# 05_Connectors_LDO_EEPROM.net
KiCad netlist of a schematic drawn in Altium Designer
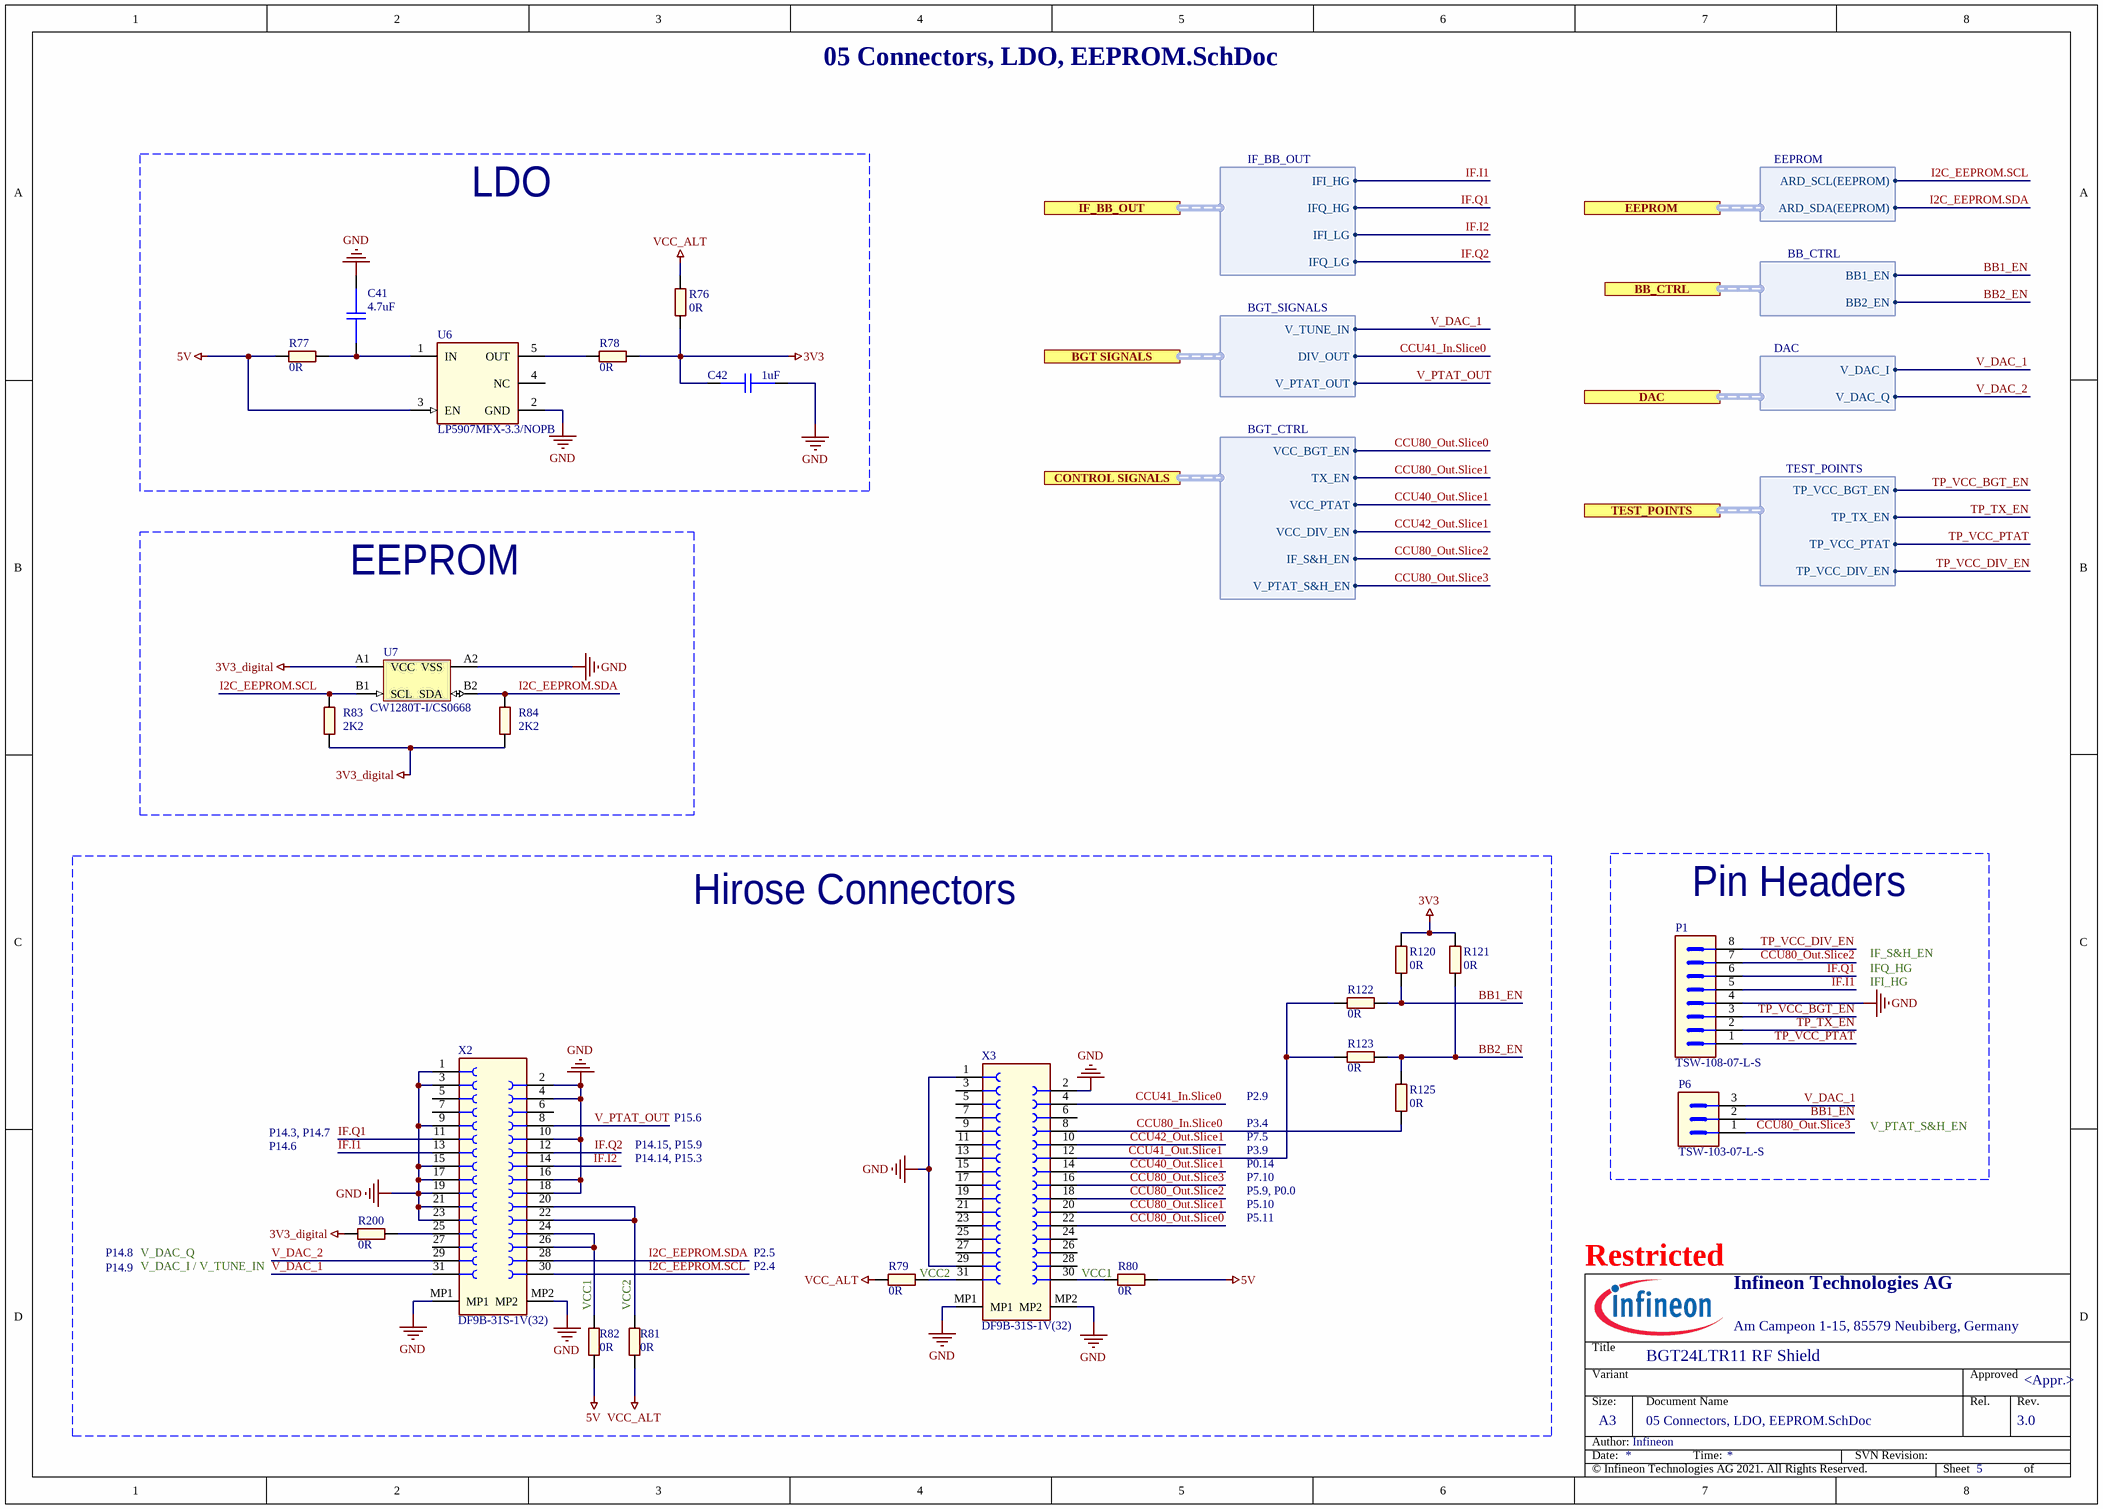
[diagram p0: 05 Connectors, LDO, EEPROM.SchDoc]

(export (version "E")
  (design (tool "Eeschema 10.0.6"))
  (components
    (comp (ref "C41")
      (value "4.7uF")
      (footprint "CAPC1005X55N-0_2")
      (description "General Purpose Surface Mount Ceramic Capacitor")
      (fields (field (name "PARTNUMBER") "CAP01010597") (field (name "VOLTAGE") "50Vdc"))
      (libsource (lib "DB_External_Capacitor") (part "c_std_a"))
    )
    (comp (ref "C42")
      (value "1uF")
      (footprint "CAPC1005X55N-0_2")
      (description "General Purpose Surface Mount Ceramic Capacitor")
      (fields (field (name "PARTNUMBER") "CAP01010597") (field (name "VOLTAGE") "50Vdc"))
      (libsource (lib "DB_External_Capacitor") (part "c_std_a"))
    )
    (comp (ref "P1")
      (value "TSW-108-07-L-S")
      (footprint "CON-M-THT-TSW-108-07-L-S")
      (description "Through hole .025'' SQ Post Header, 2.54mm pitch, 8 pin, vertical, single row")
      (fields (field (name "LEGACY PARTNUMBER") "CON01500577") (field (name "MANUFACTURER") "Samtec"))
      (libsource (lib "PCBLibraryData") (part "Header 8"))
    )
    (comp (ref "P6")
      (value "TSW-103-07-L-S")
      (footprint "CON-M-THT-TSW-103-07-L-S")
      (description "Through hole .025 SQ Post Header, 2.54mm pitch, 3 pin, vertical, single row")
      (fields (field (name "LEGACY PARTNUMBER") "CON01500575") (field (name "MANUFACTURER") "Samtec"))
      (libsource (lib "PCBLibraryData") (part "Header 3"))
    )
    (comp (ref "R76")
      (value "0R")
      (footprint "RESC1005X40N_2")
      (description "0R/50V/20mOhm")
      (fields (field (name "PARTNUMBER") "RES01800000") (field (name "POWER") "1.5A"))
      (libsource (lib "") (part "r_std_a_1"))
    )
    (comp (ref "R77")
      (value "0R")
      (footprint "RESC1005X40N_2")
      (description "0R/50V/20mOhm")
      (fields (field (name "PARTNUMBER") "RES01800000") (field (name "POWER") "1.5A"))
      (libsource (lib "") (part "r_std_a_2"))
    )
    (comp (ref "R78")
      (value "0R")
      (footprint "RESC1005X40N_2")
      (description "0R/50V/20mOhm")
      (fields (field (name "PARTNUMBER") "RES01800000") (field (name "POWER") "1.5A"))
      (libsource (lib "") (part "r_std_a_2"))
    )
    (comp (ref "R79")
      (value "0R")
      (footprint "RESC1005X40N_2")
      (description "0R/50V/20mOhm")
      (fields (field (name "PARTNUMBER") "RES01800000") (field (name "POWER") "1.5A"))
      (libsource (lib "") (part "r_std_a_3"))
    )
    (comp (ref "R80")
      (value "0R")
      (footprint "RESC1005X40N_2")
      (description "0R/50V/20mOhm")
      (fields (field (name "PARTNUMBER") "RES01800000") (field (name "POWER") "1.5A"))
      (libsource (lib "") (part "r_std_a_2"))
    )
    (comp (ref "R81")
      (value "0R")
      (footprint "RESC1005X40N_2")
      (description "0R/50V/20mOhm")
      (fields (field (name "PARTNUMBER") "RES01800000") (field (name "POWER") "1.5A"))
      (libsource (lib "DB_External_Resistor") (part "r_std_a"))
    )
    (comp (ref "R82")
      (value "0R")
      (footprint "RESC1005X40N_2")
      (description "0R/50V/20mOhm")
      (fields (field (name "PARTNUMBER") "RES01800000") (field (name "POWER") "1.5A"))
      (libsource (lib "DB_External_Resistor") (part "r_std_a"))
    )
    (comp (ref "R83")
      (value "2K2")
      (footprint "RESC1005X40N_2")
      (description "2K2/50V/20mOhm")
      (fields (field (name "PARTNUMBER") "RES01800000") (field (name "POWER") "1.5A"))
      (libsource (lib "") (part "r_std_a_1"))
    )
    (comp (ref "R84")
      (value "2K2")
      (footprint "RESC1005X40N_2")
      (description "2K2/50V/20mOhm")
      (fields (field (name "PARTNUMBER") "RES01800000") (field (name "POWER") "1.5A"))
      (libsource (lib "") (part "r_std_a_1"))
    )
    (comp (ref "R120")
      (value "0R")
      (footprint "RESC1005X40N_2")
      (description "0R/50V/20mOhm")
      (fields (field (name "PARTNUMBER") "RES01800000") (field (name "POWER") "1.5A"))
      (libsource (lib "") (part "r_std_a_1"))
    )
    (comp (ref "R121")
      (value "0R")
      (footprint "RESC1005X40N_2")
      (description "0R/50V/20mOhm")
      (fields (field (name "PARTNUMBER") "RES01800000") (field (name "POWER") "1.5A"))
      (libsource (lib "") (part "r_std_a_1"))
    )
    (comp (ref "R122")
      (value "0R")
      (footprint "RESC1005X40N_2")
      (description "0R/50V/20mOhm")
      (fields (field (name "PARTNUMBER") "RES01800000") (field (name "POWER") "1.5A"))
      (libsource (lib "") (part "r_std_a_2"))
    )
    (comp (ref "R123")
      (value "0R")
      (footprint "RESC1005X40N_2")
      (description "0R/50V/20mOhm")
      (fields (field (name "PARTNUMBER") "RES01800000") (field (name "POWER") "1.5A"))
      (libsource (lib "") (part "r_std_a_2"))
    )
    (comp (ref "R125")
      (value "0R")
      (footprint "RESC1005X40N_2")
      (description "0R/50V/20mOhm")
      (fields (field (name "PARTNUMBER") "RES01800000") (field (name "POWER") "1.5A"))
      (libsource (lib "") (part "r_std_a_1"))
    )
    (comp (ref "R200")
      (value "0R")
      (footprint "RESC1005X40N_2")
      (description "0R/50V/20mOhm")
      (fields (field (name "PARTNUMBER") "RES01800000") (field (name "POWER") "1.5A"))
      (libsource (lib "") (part "r_std_a_2"))
    )
    (comp (ref "U6")
      (value "LP5907MFX-3.3/NOPB")
      (footprint "SOT95P280X145-5N-2")
      (description "250mA Ultra-Low-Noise, Low-IQ LDO, 3.3V")
      (fields
        (field (name "PARTNUMBER") "IC02601280")
        (field (name "COMPONENTNAME") "LP5907MFX-3.3/NOPB")
        (field (name "MANUFACTURER") "Texas Instruments")
      )
      (libsource (lib "DB_External_IC") (part "LP5907MFX"))
    )
    (comp (ref "U7")
      (value "CW1280T-I/CS0668")
      (footprint "WLCSP4 (CS0)")
      (description "128K I2C Serial EEPROM with Software Write Protection in CSP4 Package, 0.4mm Pin Pitch")
      (libsource (lib "BGT24LTR11 RF-Shield Board V0.3") (part "24CW128X"))
    )
    (comp (ref "X2")
      (value "DF9B-31S-1V(32)")
      (footprint "CON-F-SMD-DF9B-31S-1V-32-1")
      (description "SMT Board-to-Board connectors-standard interface connector")
      (fields (field (name "MANUFACTURER") "Hirose Connectors"))
      (libsource (lib "PCBLibraryData") (part "CON-SOC-016X002-0031P-02S-00M_00080644"))
    )
    (comp (ref "X3")
      (value "DF9B-31S-1V(32)")
      (footprint "CON-F-SMD-DF9B-31S-1V-32-1")
      (description "SMT Board-to-Board connectors-standard interface connector")
      (fields (field (name "MANUFACTURER") "Hirose Connectors"))
      (libsource (lib "PCBLibraryData") (part "CON-SOC-016X002-0031P-02S-00M_00080644"))
    )
  )
  (nets
    (net (code "8") (name "/BB1_EN") (class "Default")
      (node (ref "P6") (pin "2") (pinfunction "2_2") (pintype "passive"))
      (node (ref "R120") (pin "2") (pinfunction "2_2") (pintype "passive"))
      (node (ref "R122") (pin "1") (pinfunction "1_1") (pintype "passive"))
    )
    (net (code "9") (name "/BB2_EN") (class "Default")
      (node (ref "R121") (pin "2") (pinfunction "2_2") (pintype "passive"))
      (node (ref "R123") (pin "1") (pinfunction "1_1") (pintype "passive"))
      (node (ref "R125") (pin "1") (pinfunction "1_1") (pintype "passive"))
    )
    (net (code "10") (name "/CCU40_Out.Slice1") (class "Default")
      (node (ref "X3") (pin "14") (pinfunction "14_14") (pintype "passive"))
    )
    (net (code "11") (name "/CCU41_In.Slice0") (class "Default")
      (node (ref "X3") (pin "4") (pinfunction "4_4") (pintype "passive"))
    )
    (net (code "12") (name "/CCU41_Out.Slice1") (class "Default")
      (node (ref "R122") (pin "2") (pinfunction "2_2") (pintype "passive"))
      (node (ref "R123") (pin "2") (pinfunction "2_2") (pintype "passive"))
      (node (ref "X3") (pin "12") (pinfunction "12_12") (pintype "passive"))
    )
    (net (code "13") (name "/CCU42_Out.Slice1") (class "Default")
      (node (ref "X3") (pin "10") (pinfunction "10_10") (pintype "passive"))
    )
    (net (code "14") (name "/CCU80_In.Slice0") (class "Default")
      (node (ref "R125") (pin "2") (pinfunction "2_2") (pintype "passive"))
      (node (ref "X3") (pin "8") (pinfunction "8_8") (pintype "passive"))
    )
    (net (code "15") (name "/CCU80_Out.Slice0") (class "Default")
      (node (ref "X3") (pin "22") (pinfunction "22_22") (pintype "passive"))
    )
    (net (code "16") (name "/CCU80_Out.Slice1") (class "Default")
      (node (ref "X3") (pin "20") (pinfunction "20_20") (pintype "passive"))
    )
    (net (code "17") (name "/CCU80_Out.Slice2") (class "Default")
      (node (ref "P1") (pin "7") (pinfunction "7_7") (pintype "passive"))
      (node (ref "X3") (pin "18") (pinfunction "18_18") (pintype "passive"))
    )
    (net (code "18") (name "/CCU80_Out.Slice3") (class "Default")
      (node (ref "P6") (pin "1") (pinfunction "1_1") (pintype "passive"))
      (node (ref "X3") (pin "16") (pinfunction "16_16") (pintype "passive"))
    )
    (net (code "19") (name "/I2C_EEPROM.SCL") (class "Default")
      (node (ref "R83") (pin "1") (pinfunction "1_1") (pintype "passive"))
      (node (ref "U7") (pin "B1") (pinfunction "SCL_B1") (pintype "input"))
      (node (ref "X2") (pin "30") (pinfunction "30_30") (pintype "passive"))
    )
    (net (code "20") (name "/I2C_EEPROM.SDA") (class "Default")
      (node (ref "R84") (pin "1") (pinfunction "1_1") (pintype "passive"))
      (node (ref "U7") (pin "B2") (pinfunction "SDA_B2") (pintype "bidirectional"))
      (node (ref "X2") (pin "28") (pinfunction "28_28") (pintype "passive"))
    )
    (net (code "21") (name "/IF.I1") (class "Default")
      (node (ref "P1") (pin "5") (pinfunction "5_5") (pintype "passive"))
      (node (ref "X2") (pin "13") (pinfunction "13_13") (pintype "passive"))
    )
    (net (code "22") (name "/IF.I2") (class "Default")
      (node (ref "X2") (pin "14") (pinfunction "14_14") (pintype "passive"))
    )
    (net (code "23") (name "/IF.Q1") (class "Default")
      (node (ref "P1") (pin "6") (pinfunction "6_6") (pintype "passive"))
      (node (ref "X2") (pin "11") (pinfunction "11_11") (pintype "passive"))
    )
    (net (code "24") (name "/IF.Q2") (class "Default")
      (node (ref "X2") (pin "12") (pinfunction "12_12") (pintype "passive"))
    )
    (net (code "25") (name "/TP_TX_EN") (class "Default")
      (node (ref "P1") (pin "2") (pinfunction "2_2") (pintype "passive"))
    )
    (net (code "26") (name "/TP_VCC_BGT_EN") (class "Default")
      (node (ref "P1") (pin "3") (pinfunction "3_3") (pintype "passive"))
    )
    (net (code "27") (name "/TP_VCC_DIV_EN") (class "Default")
      (node (ref "P1") (pin "8") (pinfunction "8_8") (pintype "passive"))
    )
    (net (code "28") (name "/TP_VCC_PTAT") (class "Default")
      (node (ref "P1") (pin "1") (pinfunction "1_1") (pintype "passive"))
    )
    (net (code "29") (name "/V_DAC_1") (class "Default")
      (node (ref "P6") (pin "3") (pinfunction "3_3") (pintype "passive"))
      (node (ref "X2") (pin "31") (pinfunction "31_31") (pintype "passive"))
    )
    (net (code "30") (name "/V_DAC_2") (class "Default")
      (node (ref "X2") (pin "29") (pinfunction "29_29") (pintype "passive"))
    )
    (net (code "31") (name "/V_PTAT_OUT") (class "Default")
      (node (ref "X2") (pin "8") (pinfunction "8_8") (pintype "passive"))
    )
    (net (code "39") (name "3V3") (class "Default")
      (node (ref "C42") (pin "2") (pinfunction "2_2") (pintype "passive"))
      (node (ref "R120") (pin "1") (pinfunction "1_1") (pintype "passive"))
      (node (ref "R121") (pin "1") (pinfunction "1_1") (pintype "passive"))
      (node (ref "R76") (pin "2") (pinfunction "2_2") (pintype "passive"))
      (node (ref "R78") (pin "1") (pinfunction "1_1") (pintype "passive"))
    )
    (net (code "40") (name "3V3_digital") (class "Default")
      (node (ref "R200") (pin "2") (pinfunction "2_2") (pintype "passive"))
      (node (ref "R83") (pin "2") (pinfunction "2_2") (pintype "passive"))
      (node (ref "R84") (pin "2") (pinfunction "2_2") (pintype "passive"))
      (node (ref "U7") (pin "A1") (pinfunction "VCC_A1") (pintype "passive"))
    )
    (net (code "41") (name "5V") (class "Default")
      (node (ref "R77") (pin "2") (pinfunction "2_2") (pintype "passive"))
      (node (ref "R80") (pin "1") (pinfunction "1_1") (pintype "passive"))
      (node (ref "R82") (pin "1") (pinfunction "1_1") (pintype "passive"))
      (node (ref "U6") (pin "3") (pinfunction "EN_3") (pintype "input"))
    )
    (net (code "42") (name "GND") (class "Default")
      (node (ref "C41") (pin "1") (pinfunction "1_1") (pintype "passive"))
      (node (ref "C42") (pin "1") (pinfunction "1_1") (pintype "passive"))
      (node (ref "P1") (pin "4") (pinfunction "4_4") (pintype "passive"))
      (node (ref "U6") (pin "2") (pinfunction "GND_2") (pintype "power_in"))
      (node (ref "U7") (pin "A2") (pinfunction "VSS_A2") (pintype "passive"))
      (node (ref "X2") (pin "1") (pinfunction "1_1") (pintype "passive"))
      (node (ref "X2") (pin "10") (pinfunction "10_10") (pintype "passive"))
      (node (ref "X2") (pin "15") (pinfunction "15_15") (pintype "passive"))
      (node (ref "X2") (pin "16") (pinfunction "16_16") (pintype "passive"))
      (node (ref "X2") (pin "17") (pinfunction "17_17") (pintype "passive"))
      (node (ref "X2") (pin "18") (pinfunction "18_18") (pintype "passive"))
      (node (ref "X2") (pin "19") (pinfunction "19_19") (pintype "passive"))
      (node (ref "X2") (pin "2") (pinfunction "2_2") (pintype "passive"))
      (node (ref "X2") (pin "21") (pinfunction "21_21") (pintype "passive"))
      (node (ref "X2") (pin "23") (pinfunction "23_23") (pintype "passive"))
      (node (ref "X2") (pin "3") (pinfunction "3_3") (pintype "passive"))
      (node (ref "X2") (pin "4") (pinfunction "4_4") (pintype "passive"))
      (node (ref "X2") (pin "9") (pinfunction "9_9") (pintype "passive"))
      (node (ref "X2") (pin "MP1") (pinfunction "MP1_MP1") (pintype "passive"))
      (node (ref "X2") (pin "MP2") (pinfunction "MP2_MP2") (pintype "passive"))
      (node (ref "X3") (pin "1") (pinfunction "1_1") (pintype "passive"))
      (node (ref "X3") (pin "2") (pinfunction "2_2") (pintype "passive"))
      (node (ref "X3") (pin "29") (pinfunction "29_29") (pintype "passive"))
      (node (ref "X3") (pin "MP1") (pinfunction "MP1_MP1") (pintype "passive"))
      (node (ref "X3") (pin "MP2") (pinfunction "MP2_MP2") (pintype "passive"))
    )
    (net (code "43") (name "Net-(R79-Pad2)") (class "Default")
      (node (ref "R79") (pin "2") (pinfunction "2_2") (pintype "passive"))
      (node (ref "X3") (pin "31") (pinfunction "31_31") (pintype "passive"))
    )
    (net (code "44") (name "Net-(R80-Pad2)") (class "Default")
      (node (ref "R80") (pin "2") (pinfunction "2_2") (pintype "passive"))
      (node (ref "X3") (pin "30") (pinfunction "30_30") (pintype "passive"))
    )
    (net (code "45") (name "Net-(R81-Pad2)") (class "Default")
      (node (ref "R81") (pin "2") (pinfunction "2_2") (pintype "passive"))
      (node (ref "X2") (pin "20") (pinfunction "20_20") (pintype "passive"))
      (node (ref "X2") (pin "22") (pinfunction "22_22") (pintype "passive"))
    )
    (net (code "46") (name "Net-(R82-Pad2)") (class "Default")
      (node (ref "R82") (pin "2") (pinfunction "2_2") (pintype "passive"))
      (node (ref "X2") (pin "24") (pinfunction "24_24") (pintype "passive"))
      (node (ref "X2") (pin "26") (pinfunction "26_26") (pintype "passive"))
    )
    (net (code "47") (name "Net-(R200-Pad1)") (class "Default")
      (node (ref "R200") (pin "1") (pinfunction "1_1") (pintype "passive"))
      (node (ref "X2") (pin "25") (pinfunction "25_25") (pintype "passive"))
    )
    (net (code "48") (name "Net-(U6-IN)") (class "Default")
      (node (ref "C41") (pin "2") (pinfunction "2_2") (pintype "passive"))
      (node (ref "R77") (pin "1") (pinfunction "1_1") (pintype "passive"))
      (node (ref "U6") (pin "1") (pinfunction "IN_1") (pintype "power_in"))
    )
    (net (code "49") (name "Net-(U6-OUT)") (class "Default")
      (node (ref "R78") (pin "2") (pinfunction "2_2") (pintype "passive"))
      (node (ref "U6") (pin "5") (pinfunction "OUT_5") (pintype "power_in"))
    )
    (net (code "50") (name "VCC_ALT") (class "Default")
      (node (ref "R76") (pin "1") (pinfunction "1_1") (pintype "passive"))
      (node (ref "R79") (pin "1") (pinfunction "1_1") (pintype "passive"))
      (node (ref "R81") (pin "1") (pinfunction "1_1") (pintype "passive"))
    )
    (net (code "51") (name "unconnected-(U6-NC-Pad4)") (class "Default")
      (node (ref "U6") (pin "4") (pinfunction "NC_4") (pintype "passive"))
    )
    (net (code "52") (name "unconnected-(X2-Pad5)") (class "Default")
      (node (ref "X2") (pin "5") (pinfunction "5_5") (pintype "passive"))
    )
    (net (code "53") (name "unconnected-(X2-Pad6)") (class "Default")
      (node (ref "X2") (pin "6") (pinfunction "6_6") (pintype "passive"))
    )
    (net (code "54") (name "unconnected-(X2-Pad7)") (class "Default")
      (node (ref "X2") (pin "7") (pinfunction "7_7") (pintype "passive"))
    )
    (net (code "55") (name "unconnected-(X2-Pad27)") (class "Default")
      (node (ref "X2") (pin "27") (pinfunction "27_27") (pintype "passive"))
    )
    (net (code "56") (name "unconnected-(X3-Pad3)") (class "Default")
      (node (ref "X3") (pin "3") (pinfunction "3_3") (pintype "passive"))
    )
    (net (code "57") (name "unconnected-(X3-Pad5)") (class "Default")
      (node (ref "X3") (pin "5") (pinfunction "5_5") (pintype "passive"))
    )
    (net (code "58") (name "unconnected-(X3-Pad6)") (class "Default")
      (node (ref "X3") (pin "6") (pinfunction "6_6") (pintype "passive"))
    )
    (net (code "59") (name "unconnected-(X3-Pad7)") (class "Default")
      (node (ref "X3") (pin "7") (pinfunction "7_7") (pintype "passive"))
    )
    (net (code "60") (name "unconnected-(X3-Pad9)") (class "Default")
      (node (ref "X3") (pin "9") (pinfunction "9_9") (pintype "passive"))
    )
    (net (code "61") (name "unconnected-(X3-Pad11)") (class "Default")
      (node (ref "X3") (pin "11") (pinfunction "11_11") (pintype "passive"))
    )
    (net (code "62") (name "unconnected-(X3-Pad13)") (class "Default")
      (node (ref "X3") (pin "13") (pinfunction "13_13") (pintype "passive"))
    )
    (net (code "63") (name "unconnected-(X3-Pad15)") (class "Default")
      (node (ref "X3") (pin "15") (pinfunction "15_15") (pintype "passive"))
    )
    (net (code "64") (name "unconnected-(X3-Pad17)") (class "Default")
      (node (ref "X3") (pin "17") (pinfunction "17_17") (pintype "passive"))
    )
    (net (code "65") (name "unconnected-(X3-Pad19)") (class "Default")
      (node (ref "X3") (pin "19") (pinfunction "19_19") (pintype "passive"))
    )
    (net (code "66") (name "unconnected-(X3-Pad21)") (class "Default")
      (node (ref "X3") (pin "21") (pinfunction "21_21") (pintype "passive"))
    )
    (net (code "67") (name "unconnected-(X3-Pad23)") (class "Default")
      (node (ref "X3") (pin "23") (pinfunction "23_23") (pintype "passive"))
    )
    (net (code "68") (name "unconnected-(X3-Pad24)") (class "Default")
      (node (ref "X3") (pin "24") (pinfunction "24_24") (pintype "passive"))
    )
    (net (code "69") (name "unconnected-(X3-Pad25)") (class "Default")
      (node (ref "X3") (pin "25") (pinfunction "25_25") (pintype "passive"))
    )
    (net (code "70") (name "unconnected-(X3-Pad26)") (class "Default")
      (node (ref "X3") (pin "26") (pinfunction "26_26") (pintype "passive"))
    )
    (net (code "71") (name "unconnected-(X3-Pad27)") (class "Default")
      (node (ref "X3") (pin "27") (pinfunction "27_27") (pintype "passive"))
    )
    (net (code "72") (name "unconnected-(X3-Pad28)") (class "Default")
      (node (ref "X3") (pin "28") (pinfunction "28_28") (pintype "passive"))
    )
  )
)
